# MINI_BLDC_DRV_POWER.net
KiCad netlist of a schematic drawn in Altium Designer
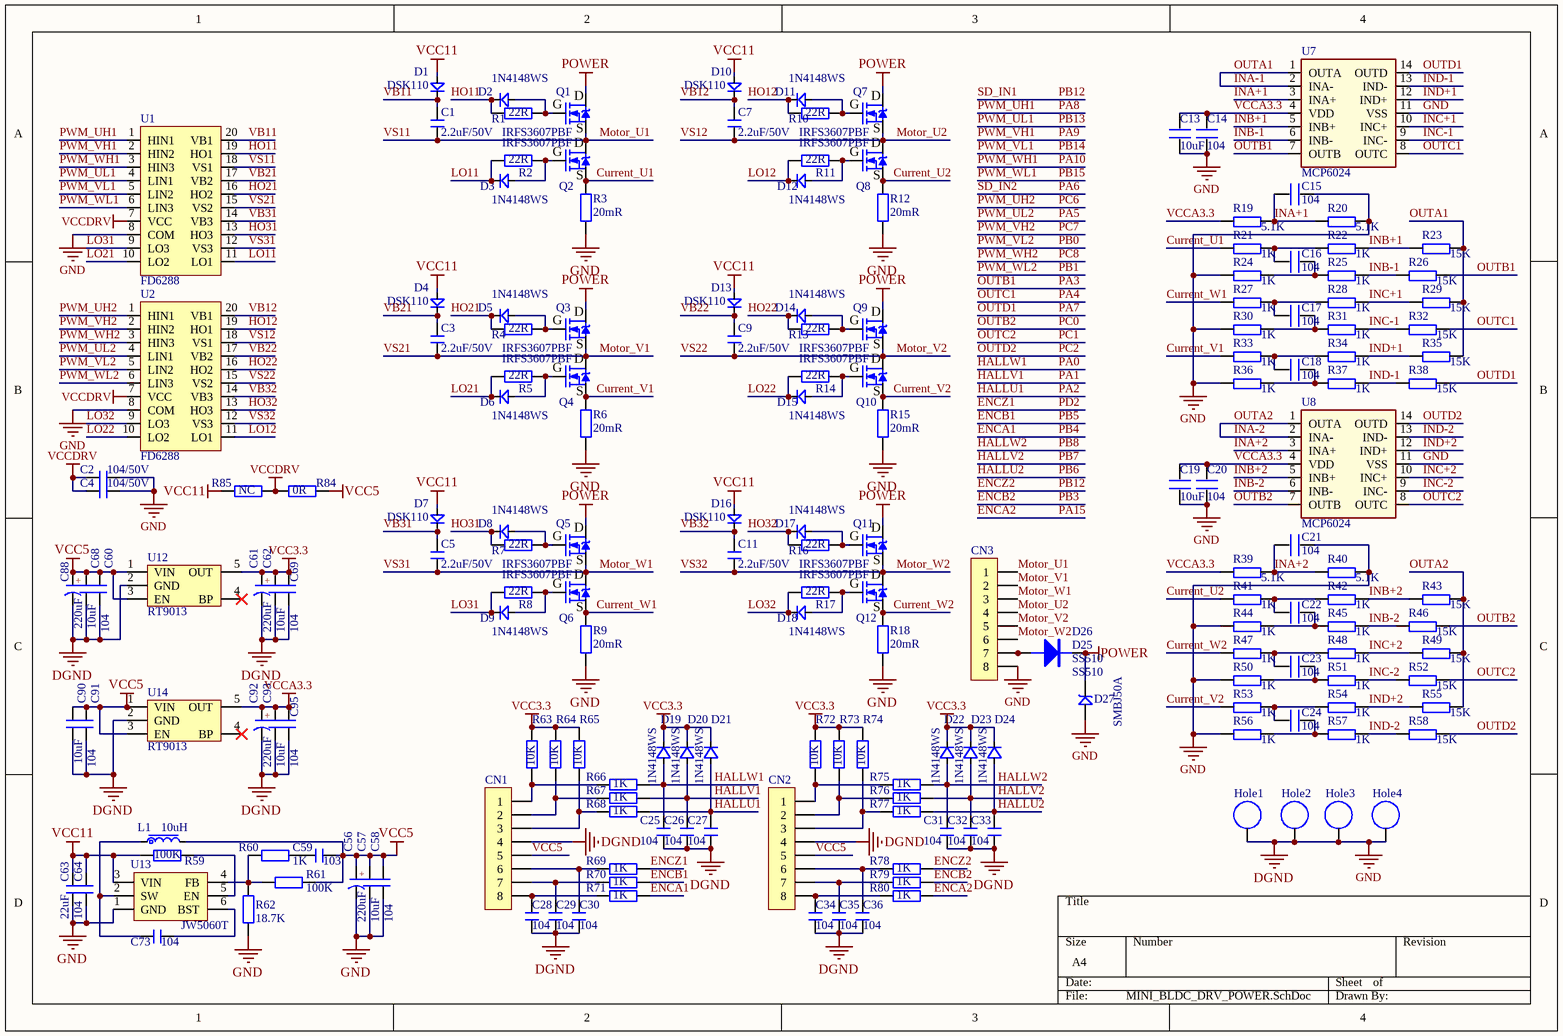
[diagram p0: MINI_BLDC_DRV_POWER.SchDoc]

(export (version "E")
  (design (tool "Eeschema 10.0.6"))
  (components
    (comp (ref "C1")
      (value "2.2uF/50V")
      (footprint "C 0603_L")
      (description "无极性贴片电容")
      (fields (field (name "版权归属") "源创客"))
      (libsource (lib "电阻-电容-电感") (part "C"))
    )
    (comp (ref "C2")
      (value "104/50V")
      (footprint "C 0603_L")
      (description "无极性贴片电容")
      (fields (field (name "版权归属") "源创客"))
      (libsource (lib "电阻-电容-电感") (part "C"))
    )
    (comp (ref "C3")
      (value "2.2uF/50V")
      (footprint "C 0603_L")
      (description "无极性贴片电容")
      (fields (field (name "版权归属") "源创客"))
      (libsource (lib "电阻-电容-电感") (part "C"))
    )
    (comp (ref "C4")
      (value "104/50V")
      (footprint "C 0603_L")
      (description "无极性贴片电容")
      (fields (field (name "版权归属") "源创客"))
      (libsource (lib "电阻-电容-电感") (part "C"))
    )
    (comp (ref "C5")
      (value "2.2uF/50V")
      (footprint "C 0603_L")
      (description "无极性贴片电容")
      (fields (field (name "版权归属") "源创客"))
      (libsource (lib "电阻-电容-电感") (part "C"))
    )
    (comp (ref "C7")
      (value "2.2uF/50V")
      (footprint "C 0603_L")
      (description "无极性贴片电容")
      (fields (field (name "版权归属") "源创客"))
      (libsource (lib "电阻-电容-电感") (part "C"))
    )
    (comp (ref "C9")
      (value "2.2uF/50V")
      (footprint "C 0603_L")
      (description "无极性贴片电容")
      (fields (field (name "版权归属") "源创客"))
      (libsource (lib "电阻-电容-电感") (part "C"))
    )
    (comp (ref "C11")
      (value "2.2uF/50V")
      (footprint "C 0603_L")
      (description "无极性贴片电容")
      (fields (field (name "版权归属") "源创客"))
      (libsource (lib "电阻-电容-电感") (part "C"))
    )
    (comp (ref "C13")
      (value "10uF")
      (footprint "C 0603_L")
      (libsource (lib "IMX6UL_ALPHA(底板)_V2.0") (part "C"))
    )
    (comp (ref "C14")
      (value "104")
      (footprint "C 0603_L")
      (libsource (lib "IMX6UL_ALPHA(底板)_V2.0") (part "C"))
    )
    (comp (ref "C15")
      (value "104")
      (footprint "C 0603_L")
      (libsource (lib "IMX6UL_ALPHA(底板)_V2.0") (part "C"))
    )
    (comp (ref "C16")
      (value "104")
      (footprint "C 0603_L")
      (libsource (lib "IMX6UL_ALPHA(底板)_V2.0") (part "C"))
    )
    (comp (ref "C17")
      (value "104")
      (footprint "C 0603_L")
      (libsource (lib "IMX6UL_ALPHA(底板)_V2.0") (part "C"))
    )
    (comp (ref "C18")
      (value "104")
      (footprint "C 0603_L")
      (libsource (lib "IMX6UL_ALPHA(底板)_V2.0") (part "C"))
    )
    (comp (ref "C19")
      (value "10uF")
      (footprint "C 0603_L")
      (libsource (lib "IMX6UL_ALPHA(底板)_V2.0") (part "C"))
    )
    (comp (ref "C20")
      (value "104")
      (footprint "C 0603_L")
      (libsource (lib "IMX6UL_ALPHA(底板)_V2.0") (part "C"))
    )
    (comp (ref "C21")
      (value "104")
      (footprint "C 0603_L")
      (libsource (lib "IMX6UL_ALPHA(底板)_V2.0") (part "C"))
    )
    (comp (ref "C22")
      (value "104")
      (footprint "C 0603_L")
      (libsource (lib "IMX6UL_ALPHA(底板)_V2.0") (part "C"))
    )
    (comp (ref "C23")
      (value "104")
      (footprint "C 0603_L")
      (libsource (lib "IMX6UL_ALPHA(底板)_V2.0") (part "C"))
    )
    (comp (ref "C24")
      (value "104")
      (footprint "C 0603_L")
      (libsource (lib "IMX6UL_ALPHA(底板)_V2.0") (part "C"))
    )
    (comp (ref "C25")
      (value "104")
      (footprint "C 0603_L")
      (description "无极性贴片电容")
      (fields (field (name "版权归属") "源创客"))
      (libsource (lib "电阻-电容-电感") (part "C"))
    )
    (comp (ref "C26")
      (value "104")
      (footprint "C 0603_L")
      (description "无极性贴片电容")
      (fields (field (name "版权归属") "源创客"))
      (libsource (lib "电阻-电容-电感") (part "C"))
    )
    (comp (ref "C27")
      (value "104")
      (footprint "C 0603_L")
      (description "无极性贴片电容")
      (fields (field (name "版权归属") "源创客"))
      (libsource (lib "电阻-电容-电感") (part "C"))
    )
    (comp (ref "C28")
      (value "104")
      (footprint "C 0603_L")
      (description "无极性贴片电容")
      (fields (field (name "版权归属") "源创客"))
      (libsource (lib "电阻-电容-电感") (part "C"))
    )
    (comp (ref "C29")
      (value "104")
      (footprint "C 0603_L")
      (description "无极性贴片电容")
      (fields (field (name "版权归属") "源创客"))
      (libsource (lib "电阻-电容-电感") (part "C"))
    )
    (comp (ref "C30")
      (value "104")
      (footprint "C 0603_L")
      (description "无极性贴片电容")
      (fields (field (name "版权归属") "源创客"))
      (libsource (lib "电阻-电容-电感") (part "C"))
    )
    (comp (ref "C31")
      (value "104")
      (footprint "C 0603_L")
      (description "无极性贴片电容")
      (fields (field (name "版权归属") "源创客"))
      (libsource (lib "电阻-电容-电感") (part "C"))
    )
    (comp (ref "C32")
      (value "104")
      (footprint "C 0603_L")
      (description "无极性贴片电容")
      (fields (field (name "版权归属") "源创客"))
      (libsource (lib "电阻-电容-电感") (part "C"))
    )
    (comp (ref "C33")
      (value "104")
      (footprint "C 0603_L")
      (description "无极性贴片电容")
      (fields (field (name "版权归属") "源创客"))
      (libsource (lib "电阻-电容-电感") (part "C"))
    )
    (comp (ref "C34")
      (value "104")
      (footprint "C 0603_L")
      (description "无极性贴片电容")
      (fields (field (name "版权归属") "源创客"))
      (libsource (lib "电阻-电容-电感") (part "C"))
    )
    (comp (ref "C35")
      (value "104")
      (footprint "C 0603_L")
      (description "无极性贴片电容")
      (fields (field (name "版权归属") "源创客"))
      (libsource (lib "电阻-电容-电感") (part "C"))
    )
    (comp (ref "C36")
      (value "104")
      (footprint "C 0603_L")
      (description "无极性贴片电容")
      (fields (field (name "版权归属") "源创客"))
      (libsource (lib "电阻-电容-电感") (part "C"))
    )
    (comp (ref "C56")
      (value "220uF")
      (footprint "CM D(6.3*5.4)")
      (description "贴片电解电容")
      (fields (field (name "版权归属") "源创客"))
      (libsource (lib "电阻-电容-电感") (part "C-CM"))
    )
    (comp (ref "C57")
      (value "10uF")
      (footprint "C 0603_L")
      (description "无极性贴片电容")
      (fields (field (name "版权归属") "源创客"))
      (libsource (lib "电阻-电容-电感") (part "C"))
    )
    (comp (ref "C58")
      (value "104")
      (footprint "C 0603_L")
      (description "无极性贴片电容")
      (fields (field (name "版权归属") "源创客"))
      (libsource (lib "电阻-电容-电感") (part "C"))
    )
    (comp (ref "C59")
      (value "103")
      (footprint "C 0603_L")
      (description "无极性贴片电容")
      (fields (field (name "版权归属") "源创客"))
      (libsource (lib "电阻-电容-电感") (part "C"))
    )
    (comp (ref "C60")
      (value "104")
      (footprint "C 0603_L")
      (description "无极性贴片电容")
      (fields (field (name "版权归属") "源创客"))
      (libsource (lib "电阻-电容-电感") (part "C"))
    )
    (comp (ref "C61")
      (value "220uF")
      (footprint "CM D(6.3*5.4)")
      (description "贴片电解电容")
      (fields (field (name "版权归属") "源创客"))
      (libsource (lib "电阻-电容-电感") (part "C-CM"))
    )
    (comp (ref "C62")
      (value "10uF")
      (footprint "C 0603_L")
      (description "无极性贴片电容")
      (fields (field (name "版权归属") "源创客"))
      (libsource (lib "电阻-电容-电感") (part "C"))
    )
    (comp (ref "C63")
      (value "22uF")
      (footprint "C 0805_L")
      (description "无极性贴片电容")
      (fields (field (name "版权归属") "源创客"))
      (libsource (lib "电阻-电容-电感") (part "C"))
    )
    (comp (ref "C64")
      (value "104")
      (footprint "C 0603_L")
      (description "无极性贴片电容")
      (fields (field (name "版权归属") "源创客"))
      (libsource (lib "电阻-电容-电感") (part "C"))
    )
    (comp (ref "C68")
      (value "10uF")
      (footprint "C 0603_L")
      (description "无极性贴片电容")
      (fields (field (name "版权归属") "源创客"))
      (libsource (lib "电阻-电容-电感") (part "C"))
    )
    (comp (ref "C69")
      (value "104")
      (footprint "C 0603_L")
      (description "无极性贴片电容")
      (fields (field (name "版权归属") "源创客"))
      (libsource (lib "电阻-电容-电感") (part "C"))
    )
    (comp (ref "C73")
      (value "104")
      (footprint "C 0603_L")
      (description "无极性贴片电容")
      (fields (field (name "版权归属") "源创客"))
      (libsource (lib "电阻-电容-电感") (part "C"))
    )
    (comp (ref "C88")
      (value "220uF")
      (footprint "CM D(6.3*5.4)")
      (description "贴片电解电容")
      (fields (field (name "版权归属") "源创客"))
      (libsource (lib "电阻-电容-电感") (part "C-CM"))
    )
    (comp (ref "C90")
      (value "10uF")
      (footprint "C 0603_L")
      (description "无极性贴片电容")
      (fields (field (name "版权归属") "源创客"))
      (libsource (lib "电阻-电容-电感") (part "C"))
    )
    (comp (ref "C91")
      (value "104")
      (footprint "C 0603_L")
      (description "无极性贴片电容")
      (fields (field (name "版权归属") "源创客"))
      (libsource (lib "电阻-电容-电感") (part "C"))
    )
    (comp (ref "C92")
      (value "220uF")
      (footprint "CM D(6.3*5.4)")
      (description "贴片电解电容")
      (fields (field (name "版权归属") "源创客"))
      (libsource (lib "电阻-电容-电感") (part "C-CM"))
    )
    (comp (ref "C93")
      (value "10uF")
      (footprint "C 0603_L")
      (description "无极性贴片电容")
      (fields (field (name "版权归属") "源创客"))
      (libsource (lib "电阻-电容-电感") (part "C"))
    )
    (comp (ref "C95")
      (value "104")
      (footprint "C 0603_L")
      (description "无极性贴片电容")
      (fields (field (name "版权归属") "源创客"))
      (libsource (lib "电阻-电容-电感") (part "C"))
    )
    (comp (ref "CN1")
      (value "HDR-1X8")
      (footprint "SH1.0 S-W-8P")
      (description "8P接插件")
      (fields (field (name "版权归属") "源创客"))
      (libsource (lib "接插件") (part "Header 8"))
    )
    (comp (ref "CN2")
      (value "HDR-1X8")
      (footprint "SH1.0 S-W-8P")
      (description "8P接插件")
      (fields (field (name "版权归属") "源创客"))
      (libsource (lib "接插件") (part "Header 8"))
    )
    (comp (ref "CN3")
      (value "HDR-1X8")
      (footprint "KF7620-8P")
      (description "8P接插件")
      (fields (field (name "版权归属") "源创客"))
      (libsource (lib "接插件") (part "Header 8"))
    )
    (comp (ref "D1")
      (value "DSK110")
      (footprint "SOD-123F")
      (description "通用二极管 100V-1A")
      (fields (field (name "版权归属") "源创客"))
      (libsource (lib "二极管-整流桥") (part "DSK110"))
    )
    (comp (ref "D2")
      (value "1N4148WS")
      (footprint "SOD-323")
      (description "通用二极管 700V-1A")
      (fields (field (name "版权归属") "源创客"))
      (libsource (lib "二极管-整流桥") (part "FR107"))
    )
    (comp (ref "D3")
      (value "1N4148WS")
      (footprint "SOD-323")
      (description "通用二极管 700V-1A")
      (fields (field (name "版权归属") "源创客"))
      (libsource (lib "二极管-整流桥") (part "FR107"))
    )
    (comp (ref "D4")
      (value "DSK110")
      (footprint "SOD-123F")
      (description "通用二极管 100V-1A")
      (fields (field (name "版权归属") "源创客"))
      (libsource (lib "二极管-整流桥") (part "DSK110"))
    )
    (comp (ref "D5")
      (value "1N4148WS")
      (footprint "SOD-323")
      (description "通用二极管 700V-1A")
      (fields (field (name "版权归属") "源创客"))
      (libsource (lib "二极管-整流桥") (part "FR107"))
    )
    (comp (ref "D6")
      (value "1N4148WS")
      (footprint "SOD-323")
      (description "通用二极管 700V-1A")
      (fields (field (name "版权归属") "源创客"))
      (libsource (lib "二极管-整流桥") (part "FR107"))
    )
    (comp (ref "D7")
      (value "DSK110")
      (footprint "SOD-123F")
      (description "通用二极管 100V-1A")
      (fields (field (name "版权归属") "源创客"))
      (libsource (lib "二极管-整流桥") (part "DSK110"))
    )
    (comp (ref "D8")
      (value "1N4148WS")
      (footprint "SOD-323")
      (description "通用二极管 700V-1A")
      (fields (field (name "版权归属") "源创客"))
      (libsource (lib "二极管-整流桥") (part "FR107"))
    )
    (comp (ref "D9")
      (value "1N4148WS")
      (footprint "SOD-323")
      (description "通用二极管 700V-1A")
      (fields (field (name "版权归属") "源创客"))
      (libsource (lib "二极管-整流桥") (part "FR107"))
    )
    (comp (ref "D10")
      (value "DSK110")
      (footprint "SOD-123F")
      (description "通用二极管 100V-1A")
      (fields (field (name "版权归属") "源创客"))
      (libsource (lib "二极管-整流桥") (part "DSK110"))
    )
    (comp (ref "D11")
      (value "1N4148WS")
      (footprint "SOD-323")
      (description "通用二极管 700V-1A")
      (fields (field (name "版权归属") "源创客"))
      (libsource (lib "二极管-整流桥") (part "FR107"))
    )
    (comp (ref "D12")
      (value "1N4148WS")
      (footprint "SOD-323")
      (description "通用二极管 700V-1A")
      (fields (field (name "版权归属") "源创客"))
      (libsource (lib "二极管-整流桥") (part "FR107"))
    )
    (comp (ref "D13")
      (value "DSK110")
      (footprint "SOD-123F")
      (description "通用二极管 100V-1A")
      (fields (field (name "版权归属") "源创客"))
      (libsource (lib "二极管-整流桥") (part "DSK110"))
    )
    (comp (ref "D14")
      (value "1N4148WS")
      (footprint "SOD-323")
      (description "通用二极管 700V-1A")
      (fields (field (name "版权归属") "源创客"))
      (libsource (lib "二极管-整流桥") (part "FR107"))
    )
    (comp (ref "D15")
      (value "1N4148WS")
      (footprint "SOD-323")
      (description "通用二极管 700V-1A")
      (fields (field (name "版权归属") "源创客"))
      (libsource (lib "二极管-整流桥") (part "FR107"))
    )
    (comp (ref "D16")
      (value "DSK110")
      (footprint "SOD-123F")
      (description "通用二极管 100V-1A")
      (fields (field (name "版权归属") "源创客"))
      (libsource (lib "二极管-整流桥") (part "DSK110"))
    )
    (comp (ref "D17")
      (value "1N4148WS")
      (footprint "SOD-323")
      (description "通用二极管 700V-1A")
      (fields (field (name "版权归属") "源创客"))
      (libsource (lib "二极管-整流桥") (part "FR107"))
    )
    (comp (ref "D18")
      (value "1N4148WS")
      (footprint "SOD-323")
      (description "通用二极管 700V-1A")
      (fields (field (name "版权归属") "源创客"))
      (libsource (lib "二极管-整流桥") (part "FR107"))
    )
    (comp (ref "D19")
      (value "1N4148WS")
      (footprint "SOD-323")
      (description "通用二极管 1000V-1A")
      (fields (field (name "版权归属") "源创客"))
      (libsource (lib "二极管-整流桥") (part "RS1M"))
    )
    (comp (ref "D20")
      (value "1N4148WS")
      (footprint "SOD-323")
      (description "通用二极管 1000V-1A")
      (fields (field (name "版权归属") "源创客"))
      (libsource (lib "二极管-整流桥") (part "RS1M"))
    )
    (comp (ref "D21")
      (value "1N4148WS")
      (footprint "SOD-323")
      (description "通用二极管 1000V-1A")
      (fields (field (name "版权归属") "源创客"))
      (libsource (lib "二极管-整流桥") (part "RS1M"))
    )
    (comp (ref "D22")
      (value "1N4148WS")
      (footprint "SOD-323")
      (description "通用二极管 1000V-1A")
      (fields (field (name "版权归属") "源创客"))
      (libsource (lib "二极管-整流桥") (part "RS1M"))
    )
    (comp (ref "D23")
      (value "1N4148WS")
      (footprint "SOD-323")
      (description "通用二极管 1000V-1A")
      (fields (field (name "版权归属") "源创客"))
      (libsource (lib "二极管-整流桥") (part "RS1M"))
    )
    (comp (ref "D24")
      (value "1N4148WS")
      (footprint "SOD-323")
      (description "通用二极管 1000V-1A")
      (fields (field (name "版权归属") "源创客"))
      (libsource (lib "二极管-整流桥") (part "RS1M"))
    )
    (comp (ref "D25")
      (value "SS510")
      (footprint "LovelessingPcb:SMB")
      (description "整流二极管")
      (libsource (lib "LovelessingSch") (part "DIODE"))
    )
    (comp (ref "D26")
      (value "SS510")
      (footprint "LovelessingPcb:SMB")
      (description "整流二极管")
      (libsource (lib "LovelessingSch") (part "DIODE"))
    )
    (comp (ref "D27")
      (value "SMBJ50A")
      (footprint "LovelessingPcb:SMC")
      (description "TVS")
      (libsource (lib "IMX6UL_ALPHA_V1.4") (part "SMBJ"))
    )
    (comp (ref "Hole1")
      (value "M3孔")
      (footprint "M3x4_L")
      (description "铜柱孔")
      (fields (field (name "版权归属") "源创客"))
      (libsource (lib "未分类器件") (part "M3"))
    )
    (comp (ref "Hole2")
      (value "M3孔")
      (footprint "M3x4_L")
      (description "铜柱孔")
      (fields (field (name "版权归属") "源创客"))
      (libsource (lib "未分类器件") (part "M3"))
    )
    (comp (ref "Hole3")
      (value "M3孔")
      (footprint "M3x4_L")
      (description "铜柱孔")
      (fields (field (name "版权归属") "源创客"))
      (libsource (lib "未分类器件") (part "M3"))
    )
    (comp (ref "Hole4")
      (value "M3孔")
      (footprint "M3x4_L")
      (description "铜柱孔")
      (fields (field (name "版权归属") "源创客"))
      (libsource (lib "未分类器件") (part "M3"))
    )
    (comp (ref "L1")
      (value "10uH")
      (footprint "L-SMD-0420")
      (description "功率屏蔽电感")
      (fields (field (name "版权归属") "源创客"))
      (libsource (lib "电阻-电容-电感") (part "L-CDRH"))
    )
    (comp (ref "Q1")
      (value "IRFS3607PBF")
      (footprint "TO263_3B")
      (description "NMOS 75V+80A 7.4mΩ")
      (fields (field (name "版权归属") "源创客"))
      (libsource (lib "场效应管-可控硅") (part "IRFS3607PBF"))
    )
    (comp (ref "Q2")
      (value "IRFS3607PBF")
      (footprint "TO263_3B")
      (description "NMOS 75V+80A 7.4mΩ")
      (fields (field (name "版权归属") "源创客"))
      (libsource (lib "场效应管-可控硅") (part "IRFS3607PBF"))
    )
    (comp (ref "Q3")
      (value "IRFS3607PBF")
      (footprint "TO263_3B")
      (description "NMOS 75V+80A 7.4mΩ")
      (fields (field (name "版权归属") "源创客"))
      (libsource (lib "场效应管-可控硅") (part "IRFS3607PBF"))
    )
    (comp (ref "Q4")
      (value "IRFS3607PBF")
      (footprint "TO263_3B")
      (description "NMOS 75V+80A 7.4mΩ")
      (fields (field (name "版权归属") "源创客"))
      (libsource (lib "场效应管-可控硅") (part "IRFS3607PBF"))
    )
    (comp (ref "Q5")
      (value "IRFS3607PBF")
      (footprint "TO263_3B")
      (description "NMOS 75V+80A 7.4mΩ")
      (fields (field (name "版权归属") "源创客"))
      (libsource (lib "场效应管-可控硅") (part "IRFS3607PBF"))
    )
    (comp (ref "Q6")
      (value "IRFS3607PBF")
      (footprint "TO263_3B")
      (description "NMOS 75V+80A 7.4mΩ")
      (fields (field (name "版权归属") "源创客"))
      (libsource (lib "场效应管-可控硅") (part "IRFS3607PBF"))
    )
    (comp (ref "Q7")
      (value "IRFS3607PBF")
      (footprint "TO263_3B")
      (description "NMOS 75V+80A 7.4mΩ")
      (fields (field (name "版权归属") "源创客"))
      (libsource (lib "场效应管-可控硅") (part "IRFS3607PBF"))
    )
    (comp (ref "Q8")
      (value "IRFS3607PBF")
      (footprint "TO263_3B")
      (description "NMOS 75V+80A 7.4mΩ")
      (fields (field (name "版权归属") "源创客"))
      (libsource (lib "场效应管-可控硅") (part "IRFS3607PBF"))
    )
    (comp (ref "Q9")
      (value "IRFS3607PBF")
      (footprint "TO263_3B")
      (description "NMOS 75V+80A 7.4mΩ")
      (fields (field (name "版权归属") "源创客"))
      (libsource (lib "场效应管-可控硅") (part "IRFS3607PBF"))
    )
    (comp (ref "Q10")
      (value "IRFS3607PBF")
      (footprint "TO263_3B")
      (description "NMOS 75V+80A 7.4mΩ")
      (fields (field (name "版权归属") "源创客"))
      (libsource (lib "场效应管-可控硅") (part "IRFS3607PBF"))
    )
    (comp (ref "Q11")
      (value "IRFS3607PBF")
      (footprint "TO263_3B")
      (description "NMOS 75V+80A 7.4mΩ")
      (fields (field (name "版权归属") "源创客"))
      (libsource (lib "场效应管-可控硅") (part "IRFS3607PBF"))
    )
    (comp (ref "Q12")
      (value "IRFS3607PBF")
      (footprint "TO263_3B")
      (description "NMOS 75V+80A 7.4mΩ")
      (fields (field (name "版权归属") "源创客"))
      (libsource (lib "场效应管-可控硅") (part "IRFS3607PBF"))
    )
    (comp (ref "R1")
      (value "22R")
      (footprint "R 0603_L")
      (description "贴片电阻")
      (fields (field (name "版权归属") "源创客"))
      (libsource (lib "电阻-电容-电感") (part "R"))
    )
    (comp (ref "R2")
      (value "22R")
      (footprint "R 0603_L")
      (description "贴片电阻")
      (fields (field (name "版权归属") "源创客"))
      (libsource (lib "电阻-电容-电感") (part "R"))
    )
    (comp (ref "R3")
      (value "20mR")
      (footprint "R 2512_L")
      (description "贴片电阻")
      (fields (field (name "版权归属") "源创客"))
      (libsource (lib "电阻-电容-电感") (part "R"))
    )
    (comp (ref "R4")
      (value "22R")
      (footprint "R 0603_L")
      (description "贴片电阻")
      (fields (field (name "版权归属") "源创客"))
      (libsource (lib "电阻-电容-电感") (part "R"))
    )
    (comp (ref "R5")
      (value "22R")
      (footprint "R 0603_L")
      (description "贴片电阻")
      (fields (field (name "版权归属") "源创客"))
      (libsource (lib "电阻-电容-电感") (part "R"))
    )
    (comp (ref "R6")
      (value "20mR")
      (footprint "R 2512_L")
      (description "贴片电阻")
      (fields (field (name "版权归属") "源创客"))
      (libsource (lib "电阻-电容-电感") (part "R"))
    )
    (comp (ref "R7")
      (value "22R")
      (footprint "R 0603_L")
      (description "贴片电阻")
      (fields (field (name "版权归属") "源创客"))
      (libsource (lib "电阻-电容-电感") (part "R"))
    )
    (comp (ref "R8")
      (value "22R")
      (footprint "R 0603_L")
      (description "贴片电阻")
      (fields (field (name "版权归属") "源创客"))
      (libsource (lib "电阻-电容-电感") (part "R"))
    )
    (comp (ref "R9")
      (value "20mR")
      (footprint "R 2512_L")
      (description "贴片电阻")
      (fields (field (name "版权归属") "源创客"))
      (libsource (lib "电阻-电容-电感") (part "R"))
    )
    (comp (ref "R10")
      (value "22R")
      (footprint "R 0603_L")
      (description "贴片电阻")
      (fields (field (name "版权归属") "源创客"))
      (libsource (lib "电阻-电容-电感") (part "R"))
    )
    (comp (ref "R11")
      (value "22R")
      (footprint "R 0603_L")
      (description "贴片电阻")
      (fields (field (name "版权归属") "源创客"))
      (libsource (lib "电阻-电容-电感") (part "R"))
    )
    (comp (ref "R12")
      (value "20mR")
      (footprint "R 2512_L")
      (description "贴片电阻")
      (fields (field (name "版权归属") "源创客"))
      (libsource (lib "电阻-电容-电感") (part "R"))
    )
    (comp (ref "R13")
      (value "22R")
      (footprint "R 0603_L")
      (description "贴片电阻")
      (fields (field (name "版权归属") "源创客"))
      (libsource (lib "电阻-电容-电感") (part "R"))
    )
    (comp (ref "R14")
      (value "22R")
      (footprint "R 0603_L")
      (description "贴片电阻")
      (fields (field (name "版权归属") "源创客"))
      (libsource (lib "电阻-电容-电感") (part "R"))
    )
    (comp (ref "R15")
      (value "20mR")
      (footprint "R 2512_L")
      (description "贴片电阻")
      (fields (field (name "版权归属") "源创客"))
      (libsource (lib "电阻-电容-电感") (part "R"))
    )
    (comp (ref "R16")
      (value "22R")
      (footprint "R 0603_L")
      (description "贴片电阻")
      (fields (field (name "版权归属") "源创客"))
      (libsource (lib "电阻-电容-电感") (part "R"))
    )
    (comp (ref "R17")
      (value "22R")
      (footprint "R 0603_L")
      (description "贴片电阻")
      (fields (field (name "版权归属") "源创客"))
      (libsource (lib "电阻-电容-电感") (part "R"))
    )
    (comp (ref "R18")
      (value "20mR")
      (footprint "R 2512_L")
      (description "贴片电阻")
      (fields (field (name "版权归属") "源创客"))
      (libsource (lib "电阻-电容-电感") (part "R"))
    )
    (comp (ref "R19")
      (value "5.1K")
      (footprint "R 0603_L")
      (libsource (lib "IMX6UL_ALPHA(底板)_V2.0") (part "R"))
    )
    (comp (ref "R20")
      (value "5.1K")
      (footprint "R 0603_L")
      (libsource (lib "IMX6UL_ALPHA(底板)_V2.0") (part "R"))
    )
    (comp (ref "R21")
      (value "1K")
      (footprint "R 0603_L")
      (libsource (lib "IMX6UL_ALPHA(底板)_V2.0") (part "R"))
    )
    (comp (ref "R22")
      (value "1K")
      (footprint "R 0603_L")
      (libsource (lib "IMX6UL_ALPHA(底板)_V2.0") (part "R"))
    )
    (comp (ref "R23")
      (value "15K")
      (footprint "R 0603_L")
      (libsource (lib "IMX6UL_ALPHA(底板)_V2.0") (part "R"))
    )
    (comp (ref "R24")
      (value "1K")
      (footprint "R 0603_L")
      (libsource (lib "IMX6UL_ALPHA(底板)_V2.0") (part "R"))
    )
    (comp (ref "R25")
      (value "1K")
      (footprint "R 0603_L")
      (libsource (lib "IMX6UL_ALPHA(底板)_V2.0") (part "R"))
    )
    (comp (ref "R26")
      (value "15K")
      (footprint "R 0603_L")
      (libsource (lib "IMX6UL_ALPHA(底板)_V2.0") (part "R"))
    )
    (comp (ref "R27")
      (value "1K")
      (footprint "R 0603_L")
      (libsource (lib "IMX6UL_ALPHA(底板)_V2.0") (part "R"))
    )
    (comp (ref "R28")
      (value "1K")
      (footprint "R 0603_L")
      (libsource (lib "IMX6UL_ALPHA(底板)_V2.0") (part "R"))
    )
    (comp (ref "R29")
      (value "15K")
      (footprint "R 0603_L")
      (libsource (lib "IMX6UL_ALPHA(底板)_V2.0") (part "R"))
    )
    (comp (ref "R30")
      (value "1K")
      (footprint "R 0603_L")
      (libsource (lib "IMX6UL_ALPHA(底板)_V2.0") (part "R"))
    )
    (comp (ref "R31")
      (value "1K")
      (footprint "R 0603_L")
      (libsource (lib "IMX6UL_ALPHA(底板)_V2.0") (part "R"))
    )
    (comp (ref "R32")
      (value "15K")
      (footprint "R 0603_L")
      (libsource (lib "IMX6UL_ALPHA(底板)_V2.0") (part "R"))
    )
    (comp (ref "R33")
      (value "1K")
      (footprint "R 0603_L")
      (libsource (lib "IMX6UL_ALPHA(底板)_V2.0") (part "R"))
    )
    (comp (ref "R34")
      (value "1K")
      (footprint "R 0603_L")
      (libsource (lib "IMX6UL_ALPHA(底板)_V2.0") (part "R"))
    )
    (comp (ref "R35")
      (value "15K")
      (footprint "R 0603_L")
      (libsource (lib "IMX6UL_ALPHA(底板)_V2.0") (part "R"))
    )
    (comp (ref "R36")
      (value "1K")
      (footprint "R 0603_L")
      (libsource (lib "IMX6UL_ALPHA(底板)_V2.0") (part "R"))
    )
    (comp (ref "R37")
      (value "1K")
      (footprint "R 0603_L")
      (libsource (lib "IMX6UL_ALPHA(底板)_V2.0") (part "R"))
    )
    (comp (ref "R38")
      (value "15K")
      (footprint "R 0603_L")
      (libsource (lib "IMX6UL_ALPHA(底板)_V2.0") (part "R"))
    )
    (comp (ref "R39")
      (value "5.1K")
      (footprint "R 0603_L")
      (libsource (lib "IMX6UL_ALPHA(底板)_V2.0") (part "R"))
    )
    (comp (ref "R40")
      (value "5.1K")
      (footprint "R 0603_L")
      (libsource (lib "IMX6UL_ALPHA(底板)_V2.0") (part "R"))
    )
    (comp (ref "R41")
      (value "1K")
      (footprint "R 0603_L")
      (libsource (lib "IMX6UL_ALPHA(底板)_V2.0") (part "R"))
    )
    (comp (ref "R42")
      (value "1K")
      (footprint "R 0603_L")
      (libsource (lib "IMX6UL_ALPHA(底板)_V2.0") (part "R"))
    )
    (comp (ref "R43")
      (value "15K")
      (footprint "R 0603_L")
      (libsource (lib "IMX6UL_ALPHA(底板)_V2.0") (part "R"))
    )
    (comp (ref "R44")
      (value "1K")
      (footprint "R 0603_L")
      (libsource (lib "IMX6UL_ALPHA(底板)_V2.0") (part "R"))
    )
    (comp (ref "R45")
      (value "1K")
      (footprint "R 0603_L")
      (libsource (lib "IMX6UL_ALPHA(底板)_V2.0") (part "R"))
    )
    (comp (ref "R46")
      (value "15K")
      (footprint "R 0603_L")
      (libsource (lib "IMX6UL_ALPHA(底板)_V2.0") (part "R"))
    )
    (comp (ref "R47")
      (value "1K")
      (footprint "R 0603_L")
      (libsource (lib "IMX6UL_ALPHA(底板)_V2.0") (part "R"))
    )
    (comp (ref "R48")
      (value "1K")
      (footprint "R 0603_L")
      (libsource (lib "IMX6UL_ALPHA(底板)_V2.0") (part "R"))
    )
    (comp (ref "R49")
      (value "15K")
      (footprint "R 0603_L")
      (libsource (lib "IMX6UL_ALPHA(底板)_V2.0") (part "R"))
    )
    (comp (ref "R50")
      (value "1K")
      (footprint "R 0603_L")
      (libsource (lib "IMX6UL_ALPHA(底板)_V2.0") (part "R"))
    )
    (comp (ref "R51")
      (value "1K")
      (footprint "R 0603_L")
      (libsource (lib "IMX6UL_ALPHA(底板)_V2.0") (part "R"))
    )
    (comp (ref "R52")
      (value "15K")
      (footprint "R 0603_L")
      (libsource (lib "IMX6UL_ALPHA(底板)_V2.0") (part "R"))
    )
    (comp (ref "R53")
      (value "1K")
      (footprint "R 0603_L")
      (libsource (lib "IMX6UL_ALPHA(底板)_V2.0") (part "R"))
    )
    (comp (ref "R54")
      (value "1K")
      (footprint "R 0603_L")
      (libsource (lib "IMX6UL_ALPHA(底板)_V2.0") (part "R"))
    )
    (comp (ref "R55")
      (value "15K")
      (footprint "R 0603_L")
      (libsource (lib "IMX6UL_ALPHA(底板)_V2.0") (part "R"))
    )
    (comp (ref "R56")
      (value "1K")
      (footprint "R 0603_L")
      (libsource (lib "IMX6UL_ALPHA(底板)_V2.0") (part "R"))
    )
    (comp (ref "R57")
      (value "1K")
      (footprint "R 0603_L")
      (libsource (lib "IMX6UL_ALPHA(底板)_V2.0") (part "R"))
    )
    (comp (ref "R58")
      (value "15K")
      (footprint "R 0603_L")
      (libsource (lib "IMX6UL_ALPHA(底板)_V2.0") (part "R"))
    )
    (comp (ref "R59")
      (value "100K")
      (footprint "R 0603_L")
      (description "贴片电阻")
      (fields (field (name "版权归属") "源创客"))
      (libsource (lib "电阻-电容-电感") (part "R"))
    )
    (comp (ref "R60")
      (value "1K")
      (footprint "R 0603_L")
      (description "贴片电阻")
      (fields (field (name "版权归属") "源创客"))
      (libsource (lib "电阻-电容-电感") (part "R"))
    )
    (comp (ref "R61")
      (value "100K")
      (footprint "R 0603_L")
      (description "贴片电阻")
      (fields (field (name "版权归属") "源创客"))
      (libsource (lib "电阻-电容-电感") (part "R"))
    )
    (comp (ref "R62")
      (value "18.7K")
      (footprint "R 0603_L")
      (description "贴片电阻")
      (fields (field (name "版权归属") "源创客"))
      (libsource (lib "电阻-电容-电感") (part "R"))
    )
    (comp (ref "R63")
      (value "10K")
      (footprint "R 0603_L")
      (description "贴片电阻")
      (fields (field (name "版权归属") "源创客"))
      (libsource (lib "电阻-电容-电感") (part "R"))
    )
    (comp (ref "R64")
      (value "10K")
      (footprint "R 0603_L")
      (description "贴片电阻")
      (fields (field (name "版权归属") "源创客"))
      (libsource (lib "电阻-电容-电感") (part "R"))
    )
    (comp (ref "R65")
      (value "10K")
      (footprint "R 0603_L")
      (description "贴片电阻")
      (fields (field (name "版权归属") "源创客"))
      (libsource (lib "电阻-电容-电感") (part "R"))
    )
    (comp (ref "R66")
      (value "1K")
      (footprint "R 0603_L")
      (description "贴片电阻")
      (fields (field (name "版权归属") "源创客"))
      (libsource (lib "电阻-电容-电感") (part "R"))
    )
    (comp (ref "R67")
      (value "1K")
      (footprint "R 0603_L")
      (description "贴片电阻")
      (fields (field (name "版权归属") "源创客"))
      (libsource (lib "电阻-电容-电感") (part "R"))
    )
    (comp (ref "R68")
      (value "1K")
      (footprint "R 0603_L")
      (description "贴片电阻")
      (fields (field (name "版权归属") "源创客"))
      (libsource (lib "电阻-电容-电感") (part "R"))
    )
    (comp (ref "R69")
      (value "1K")
      (footprint "R 0603_L")
      (description "贴片电阻")
      (fields (field (name "版权归属") "源创客"))
      (libsource (lib "电阻-电容-电感") (part "R"))
    )
    (comp (ref "R70")
      (value "1K")
      (footprint "R 0603_L")
      (description "贴片电阻")
      (fields (field (name "版权归属") "源创客"))
      (libsource (lib "电阻-电容-电感") (part "R"))
    )
    (comp (ref "R71")
      (value "1K")
      (footprint "R 0603_L")
      (description "贴片电阻")
      (fields (field (name "版权归属") "源创客"))
      (libsource (lib "电阻-电容-电感") (part "R"))
    )
    (comp (ref "R72")
      (value "10K")
      (footprint "R 0603_L")
      (description "贴片电阻")
      (fields (field (name "版权归属") "源创客"))
      (libsource (lib "电阻-电容-电感") (part "R"))
    )
    (comp (ref "R73")
      (value "10K")
      (footprint "R 0603_L")
      (description "贴片电阻")
      (fields (field (name "版权归属") "源创客"))
      (libsource (lib "电阻-电容-电感") (part "R"))
    )
    (comp (ref "R74")
      (value "10K")
      (footprint "R 0603_L")
      (description "贴片电阻")
      (fields (field (name "版权归属") "源创客"))
      (libsource (lib "电阻-电容-电感") (part "R"))
    )
    (comp (ref "R75")
      (value "1K")
      (footprint "R 0603_L")
      (description "贴片电阻")
      (fields (field (name "版权归属") "源创客"))
      (libsource (lib "电阻-电容-电感") (part "R"))
    )
    (comp (ref "R76")
      (value "1K")
      (footprint "R 0603_L")
      (description "贴片电阻")
      (fields (field (name "版权归属") "源创客"))
      (libsource (lib "电阻-电容-电感") (part "R"))
    )
    (comp (ref "R77")
      (value "1K")
      (footprint "R 0603_L")
      (description "贴片电阻")
      (fields (field (name "版权归属") "源创客"))
      (libsource (lib "电阻-电容-电感") (part "R"))
    )
    (comp (ref "R78")
      (value "1K")
      (footprint "R 0603_L")
      (description "贴片电阻")
      (fields (field (name "版权归属") "源创客"))
      (libsource (lib "电阻-电容-电感") (part "R"))
    )
    (comp (ref "R79")
      (value "1K")
      (footprint "R 0603_L")
      (description "贴片电阻")
      (fields (field (name "版权归属") "源创客"))
      (libsource (lib "电阻-电容-电感") (part "R"))
    )
    (comp (ref "R80")
      (value "1K")
      (footprint "R 0603_L")
      (description "贴片电阻")
      (fields (field (name "版权归属") "源创客"))
      (libsource (lib "电阻-电容-电感") (part "R"))
    )
    (comp (ref "R84")
      (value "0R")
      (footprint "R 0603_L")
      (description "贴片电阻")
      (fields (field (name "版权归属") "源创客"))
      (libsource (lib "电阻-电容-电感") (part "R"))
    )
    (comp (ref "R85")
      (value "NC")
      (footprint "R 0603_L")
      (description "贴片电阻")
      (fields (field (name "版权归属") "源创客"))
      (libsource (lib "电阻-电容-电感") (part "R"))
    )
    (comp (ref "U1") (value "FD6288") (footprint "TSSOP20_L") (libsource (lib "MINIBLDC") (part "FD6288")))
    (comp (ref "U2") (value "FD6288") (footprint "TSSOP20_L") (libsource (lib "MINIBLDC") (part "FD6288")))
    (comp (ref "U7") (value "MCP6024") (footprint "SOP14_L") (libsource (lib "MINIBLDC") (part "MCP6024")))
    (comp (ref "U8") (value "MCP6024") (footprint "SOP14_L") (libsource (lib "MINIBLDC") (part "MCP6024")))
    (comp (ref "U12")
      (value "RT9013")
      (footprint "SOT23-5N")
      (description "LDO")
      (fields (field (name "版权归属") "源创客"))
      (libsource (lib "LDO和DCDC") (part "LDO RT9193"))
    )
    (comp (ref "U13")
      (value "JW5060T")
      (footprint "SOT23-6L")
      (description "DC降压芯片")
      (libsource (lib "LDO和DCDC") (part "DC JW5060T_6"))
    )
    (comp (ref "U14")
      (value "RT9013")
      (footprint "SOT23-5N")
      (description "LDO")
      (fields (field (name "版权归属") "源创客"))
      (libsource (lib "LDO和DCDC") (part "LDO RT9193"))
    )
  )
  (nets
    (net (code "1") (name "/Current_U1") (class "Default")
      (node (ref "Q2") (pin "3") (pinfunction "S_3") (pintype "passive"))
      (node (ref "R21") (pin "1") (pintype "passive"))
      (node (ref "R3") (pin "2") (pinfunction "2_2") (pintype "passive"))
    )
    (net (code "2") (name "/Current_U2") (class "Default")
      (node (ref "Q8") (pin "3") (pinfunction "S_3") (pintype "passive"))
      (node (ref "R12") (pin "2") (pinfunction "2_2") (pintype "passive"))
      (node (ref "R41") (pin "1") (pintype "passive"))
    )
    (net (code "3") (name "/Current_V1") (class "Default")
      (node (ref "Q4") (pin "3") (pinfunction "S_3") (pintype "passive"))
      (node (ref "R33") (pin "1") (pintype "passive"))
      (node (ref "R6") (pin "2") (pinfunction "2_2") (pintype "passive"))
    )
    (net (code "4") (name "/Current_V2") (class "Default")
      (node (ref "Q10") (pin "3") (pinfunction "S_3") (pintype "passive"))
      (node (ref "R15") (pin "2") (pinfunction "2_2") (pintype "passive"))
      (node (ref "R53") (pin "1") (pintype "passive"))
    )
    (net (code "5") (name "/Current_W1") (class "Default")
      (node (ref "Q6") (pin "3") (pinfunction "S_3") (pintype "passive"))
      (node (ref "R27") (pin "1") (pintype "passive"))
      (node (ref "R9") (pin "2") (pinfunction "2_2") (pintype "passive"))
    )
    (net (code "6") (name "/Current_W2") (class "Default")
      (node (ref "Q12") (pin "3") (pinfunction "S_3") (pintype "passive"))
      (node (ref "R18") (pin "2") (pinfunction "2_2") (pintype "passive"))
      (node (ref "R47") (pin "1") (pintype "passive"))
    )
    (net (code "7") (name "/ENCA1") (class "Default")
      (node (ref "R71") (pin "2") (pinfunction "2_2") (pintype "passive"))
    )
    (net (code "8") (name "/ENCA2") (class "Default")
      (node (ref "R80") (pin "2") (pinfunction "2_2") (pintype "passive"))
    )
    (net (code "9") (name "/ENCB1") (class "Default")
      (node (ref "R70") (pin "2") (pinfunction "2_2") (pintype "passive"))
    )
    (net (code "10") (name "/ENCB2") (class "Default")
      (node (ref "R79") (pin "2") (pinfunction "2_2") (pintype "passive"))
    )
    (net (code "11") (name "/ENCZ1") (class "Default")
      (node (ref "R69") (pin "2") (pinfunction "2_2") (pintype "passive"))
    )
    (net (code "12") (name "/ENCZ2") (class "Default")
      (node (ref "R78") (pin "2") (pinfunction "2_2") (pintype "passive"))
    )
    (net (code "13") (name "/HALLU1") (class "Default")
      (node (ref "C27") (pin "1") (pinfunction "1_1") (pintype "passive"))
      (node (ref "D21") (pin "1") (pinfunction "A_1") (pintype "passive"))
      (node (ref "R68") (pin "2") (pinfunction "2_2") (pintype "passive"))
    )
    (net (code "14") (name "/HALLU2") (class "Default")
      (node (ref "C33") (pin "1") (pinfunction "1_1") (pintype "passive"))
      (node (ref "D24") (pin "1") (pinfunction "A_1") (pintype "passive"))
      (node (ref "R77") (pin "2") (pinfunction "2_2") (pintype "passive"))
    )
    (net (code "15") (name "/HALLV1") (class "Default")
      (node (ref "C26") (pin "1") (pinfunction "1_1") (pintype "passive"))
      (node (ref "D20") (pin "1") (pinfunction "A_1") (pintype "passive"))
      (node (ref "R67") (pin "2") (pinfunction "2_2") (pintype "passive"))
    )
    (net (code "16") (name "/HALLV2") (class "Default")
      (node (ref "C32") (pin "1") (pinfunction "1_1") (pintype "passive"))
      (node (ref "D23") (pin "1") (pinfunction "A_1") (pintype "passive"))
      (node (ref "R76") (pin "2") (pinfunction "2_2") (pintype "passive"))
    )
    (net (code "17") (name "/HALLW1") (class "Default")
      (node (ref "C25") (pin "1") (pinfunction "1_1") (pintype "passive"))
      (node (ref "D19") (pin "1") (pinfunction "A_1") (pintype "passive"))
      (node (ref "R66") (pin "2") (pinfunction "2_2") (pintype "passive"))
    )
    (net (code "18") (name "/HALLW2") (class "Default")
      (node (ref "C31") (pin "1") (pinfunction "1_1") (pintype "passive"))
      (node (ref "D22") (pin "1") (pinfunction "A_1") (pintype "passive"))
      (node (ref "R75") (pin "2") (pinfunction "2_2") (pintype "passive"))
    )
    (net (code "19") (name "/HO11") (class "Default")
      (node (ref "D2") (pin "2") (pinfunction "K_2") (pintype "passive"))
      (node (ref "R1") (pin "1") (pinfunction "1_1") (pintype "passive"))
      (node (ref "U1") (pin "19") (pinfunction "HO1_19") (pintype "passive"))
    )
    (net (code "20") (name "/HO12") (class "Default")
      (node (ref "D11") (pin "2") (pinfunction "K_2") (pintype "passive"))
      (node (ref "R10") (pin "1") (pinfunction "1_1") (pintype "passive"))
      (node (ref "U2") (pin "19") (pinfunction "HO1_19") (pintype "passive"))
    )
    (net (code "21") (name "/HO21") (class "Default")
      (node (ref "D5") (pin "2") (pinfunction "K_2") (pintype "passive"))
      (node (ref "R4") (pin "1") (pinfunction "1_1") (pintype "passive"))
      (node (ref "U1") (pin "16") (pinfunction "HO2_16") (pintype "passive"))
    )
    (net (code "22") (name "/HO22") (class "Default")
      (node (ref "D14") (pin "2") (pinfunction "K_2") (pintype "passive"))
      (node (ref "R13") (pin "1") (pinfunction "1_1") (pintype "passive"))
      (node (ref "U2") (pin "16") (pinfunction "HO2_16") (pintype "passive"))
    )
    (net (code "23") (name "/HO31") (class "Default")
      (node (ref "D8") (pin "2") (pinfunction "K_2") (pintype "passive"))
      (node (ref "R7") (pin "1") (pinfunction "1_1") (pintype "passive"))
      (node (ref "U1") (pin "13") (pinfunction "HO3_13") (pintype "passive"))
    )
    (net (code "24") (name "/HO32") (class "Default")
      (node (ref "D17") (pin "2") (pinfunction "K_2") (pintype "passive"))
      (node (ref "R16") (pin "1") (pinfunction "1_1") (pintype "passive"))
      (node (ref "U2") (pin "13") (pinfunction "HO3_13") (pintype "passive"))
    )
    (net (code "25") (name "/INA+1") (class "Default")
      (node (ref "C15") (pin "1") (pintype "passive"))
      (node (ref "R19") (pin "2") (pintype "passive"))
      (node (ref "R20") (pin "1") (pintype "passive"))
      (node (ref "U7") (pin "3") (pinfunction "INA+_3") (pintype "passive"))
    )
    (net (code "26") (name "/INA+2") (class "Default")
      (node (ref "C21") (pin "1") (pintype "passive"))
      (node (ref "R39") (pin "2") (pintype "passive"))
      (node (ref "R40") (pin "1") (pintype "passive"))
      (node (ref "U8") (pin "3") (pinfunction "INA+_3") (pintype "passive"))
    )
    (net (code "27") (name "/INA-1") (class "Default")
      (node (ref "R23") (pin "2") (pintype "passive"))
      (node (ref "R29") (pin "2") (pintype "passive"))
      (node (ref "R35") (pin "2") (pintype "passive"))
      (node (ref "U7") (pin "1") (pinfunction "OUTA_1") (pintype "passive"))
      (node (ref "U7") (pin "2") (pinfunction "INA-_2") (pintype "passive"))
    )
    (net (code "28") (name "/INA-2") (class "Default")
      (node (ref "R43") (pin "2") (pintype "passive"))
      (node (ref "R49") (pin "2") (pintype "passive"))
      (node (ref "R55") (pin "2") (pintype "passive"))
      (node (ref "U8") (pin "1") (pinfunction "OUTA_1") (pintype "passive"))
      (node (ref "U8") (pin "2") (pinfunction "INA-_2") (pintype "passive"))
    )
    (net (code "29") (name "/INB+1") (class "Default")
      (node (ref "R22") (pin "2") (pintype "passive"))
      (node (ref "R23") (pin "1") (pintype "passive"))
      (node (ref "U7") (pin "5") (pinfunction "INB+_5") (pintype "passive"))
    )
    (net (code "30") (name "/INB+2") (class "Default")
      (node (ref "R42") (pin "2") (pintype "passive"))
      (node (ref "R43") (pin "1") (pintype "passive"))
      (node (ref "U8") (pin "5") (pinfunction "INB+_5") (pintype "passive"))
    )
    (net (code "31") (name "/INB-1") (class "Default")
      (node (ref "R25") (pin "2") (pintype "passive"))
      (node (ref "R26") (pin "1") (pintype "passive"))
      (node (ref "U7") (pin "6") (pinfunction "INB-_6") (pintype "passive"))
    )
    (net (code "32") (name "/INB-2") (class "Default")
      (node (ref "R45") (pin "2") (pintype "passive"))
      (node (ref "R46") (pin "1") (pintype "passive"))
      (node (ref "U8") (pin "6") (pinfunction "INB-_6") (pintype "passive"))
    )
    (net (code "33") (name "/INC+1") (class "Default")
      (node (ref "R28") (pin "2") (pintype "passive"))
      (node (ref "R29") (pin "1") (pintype "passive"))
      (node (ref "U7") (pin "10") (pinfunction "INC+_10") (pintype "passive"))
    )
    (net (code "34") (name "/INC+2") (class "Default")
      (node (ref "R48") (pin "2") (pintype "passive"))
      (node (ref "R49") (pin "1") (pintype "passive"))
      (node (ref "U8") (pin "10") (pinfunction "INC+_10") (pintype "passive"))
    )
    (net (code "35") (name "/INC-1") (class "Default")
      (node (ref "R31") (pin "2") (pintype "passive"))
      (node (ref "R32") (pin "1") (pintype "passive"))
      (node (ref "U7") (pin "9") (pinfunction "INC-_9") (pintype "passive"))
    )
    (net (code "36") (name "/INC-2") (class "Default")
      (node (ref "R51") (pin "2") (pintype "passive"))
      (node (ref "R52") (pin "1") (pintype "passive"))
      (node (ref "U8") (pin "9") (pinfunction "INC-_9") (pintype "passive"))
    )
    (net (code "37") (name "/IND+1") (class "Default")
      (node (ref "R34") (pin "2") (pintype "passive"))
      (node (ref "R35") (pin "1") (pintype "passive"))
      (node (ref "U7") (pin "12") (pinfunction "IND+_12") (pintype "passive"))
    )
    (net (code "38") (name "/IND+2") (class "Default")
      (node (ref "R54") (pin "2") (pintype "passive"))
      (node (ref "R55") (pin "1") (pintype "passive"))
      (node (ref "U8") (pin "12") (pinfunction "IND+_12") (pintype "passive"))
    )
    (net (code "39") (name "/IND-1") (class "Default")
      (node (ref "R37") (pin "2") (pintype "passive"))
      (node (ref "R38") (pin "1") (pintype "passive"))
      (node (ref "U7") (pin "13") (pinfunction "IND-_13") (pintype "passive"))
    )
    (net (code "40") (name "/IND-2") (class "Default")
      (node (ref "R57") (pin "2") (pintype "passive"))
      (node (ref "R58") (pin "1") (pintype "passive"))
      (node (ref "U8") (pin "13") (pinfunction "IND-_13") (pintype "passive"))
    )
    (net (code "41") (name "/LO11") (class "Default")
      (node (ref "D3") (pin "2") (pinfunction "K_2") (pintype "passive"))
      (node (ref "R2") (pin "1") (pinfunction "1_1") (pintype "passive"))
      (node (ref "U1") (pin "11") (pinfunction "LO1_11") (pintype "passive"))
    )
    (net (code "42") (name "/LO12") (class "Default")
      (node (ref "D12") (pin "2") (pinfunction "K_2") (pintype "passive"))
      (node (ref "R11") (pin "1") (pinfunction "1_1") (pintype "passive"))
      (node (ref "U2") (pin "11") (pinfunction "LO1_11") (pintype "passive"))
    )
    (net (code "43") (name "/LO21") (class "Default")
      (node (ref "D6") (pin "2") (pinfunction "K_2") (pintype "passive"))
      (node (ref "R5") (pin "1") (pinfunction "1_1") (pintype "passive"))
      (node (ref "U1") (pin "10") (pinfunction "LO2_10") (pintype "passive"))
    )
    (net (code "44") (name "/LO22") (class "Default")
      (node (ref "D15") (pin "2") (pinfunction "K_2") (pintype "passive"))
      (node (ref "R14") (pin "1") (pinfunction "1_1") (pintype "passive"))
      (node (ref "U2") (pin "10") (pinfunction "LO2_10") (pintype "passive"))
    )
    (net (code "45") (name "/LO31") (class "Default")
      (node (ref "D9") (pin "2") (pinfunction "K_2") (pintype "passive"))
      (node (ref "R8") (pin "1") (pinfunction "1_1") (pintype "passive"))
      (node (ref "U1") (pin "9") (pinfunction "LO3_9") (pintype "passive"))
    )
    (net (code "46") (name "/LO32") (class "Default")
      (node (ref "D18") (pin "2") (pinfunction "K_2") (pintype "passive"))
      (node (ref "R17") (pin "1") (pinfunction "1_1") (pintype "passive"))
      (node (ref "U2") (pin "9") (pinfunction "LO3_9") (pintype "passive"))
    )
    (net (code "47") (name "/Motor_U1") (class "Default")
      (node (ref "C1") (pin "1") (pinfunction "1_1") (pintype "passive"))
      (node (ref "CN3") (pin "1") (pinfunction "1_1") (pintype "passive"))
      (node (ref "Q1") (pin "3") (pinfunction "S_3") (pintype "passive"))
      (node (ref "Q2") (pin "2") (pinfunction "D_2") (pintype "passive"))
      (node (ref "U1") (pin "18") (pinfunction "VS1_18") (pintype "passive"))
    )
    (net (code "48") (name "/Motor_U2") (class "Default")
      (node (ref "C7") (pin "1") (pinfunction "1_1") (pintype "passive"))
      (node (ref "CN3") (pin "4") (pinfunction "4_4") (pintype "passive"))
      (node (ref "Q7") (pin "3") (pinfunction "S_3") (pintype "passive"))
      (node (ref "Q8") (pin "2") (pinfunction "D_2") (pintype "passive"))
      (node (ref "U2") (pin "18") (pinfunction "VS1_18") (pintype "passive"))
    )
    (net (code "49") (name "/Motor_V1") (class "Default")
      (node (ref "C3") (pin "1") (pinfunction "1_1") (pintype "passive"))
      (node (ref "CN3") (pin "2") (pinfunction "2_2") (pintype "passive"))
      (node (ref "Q3") (pin "3") (pinfunction "S_3") (pintype "passive"))
      (node (ref "Q4") (pin "2") (pinfunction "D_2") (pintype "passive"))
      (node (ref "U1") (pin "15") (pinfunction "VS2_15") (pintype "passive"))
    )
    (net (code "50") (name "/Motor_V2") (class "Default")
      (node (ref "C9") (pin "1") (pinfunction "1_1") (pintype "passive"))
      (node (ref "CN3") (pin "5") (pinfunction "5_5") (pintype "passive"))
      (node (ref "Q10") (pin "2") (pinfunction "D_2") (pintype "passive"))
      (node (ref "Q9") (pin "3") (pinfunction "S_3") (pintype "passive"))
      (node (ref "U2") (pin "15") (pinfunction "VS2_15") (pintype "passive"))
    )
    (net (code "51") (name "/Motor_W1") (class "Default")
      (node (ref "C5") (pin "1") (pinfunction "1_1") (pintype "passive"))
      (node (ref "CN3") (pin "3") (pinfunction "3_3") (pintype "passive"))
      (node (ref "Q5") (pin "3") (pinfunction "S_3") (pintype "passive"))
      (node (ref "Q6") (pin "2") (pinfunction "D_2") (pintype "passive"))
      (node (ref "U1") (pin "12") (pinfunction "VS3_12") (pintype "passive"))
    )
    (net (code "52") (name "/Motor_W2") (class "Default")
      (node (ref "C11") (pin "1") (pinfunction "1_1") (pintype "passive"))
      (node (ref "CN3") (pin "6") (pinfunction "6_6") (pintype "passive"))
      (node (ref "Q11") (pin "3") (pinfunction "S_3") (pintype "passive"))
      (node (ref "Q12") (pin "2") (pinfunction "D_2") (pintype "passive"))
      (node (ref "U2") (pin "12") (pinfunction "VS3_12") (pintype "passive"))
    )
    (net (code "53") (name "/OUTB1") (class "Default")
      (node (ref "R26") (pin "2") (pintype "passive"))
      (node (ref "U7") (pin "7") (pinfunction "OUTB_7") (pintype "passive"))
    )
    (net (code "54") (name "/OUTB2") (class "Default")
      (node (ref "R46") (pin "2") (pintype "passive"))
      (node (ref "U8") (pin "7") (pinfunction "OUTB_7") (pintype "passive"))
    )
    (net (code "55") (name "/OUTC1") (class "Default")
      (node (ref "R32") (pin "2") (pintype "passive"))
      (node (ref "U7") (pin "8") (pinfunction "OUTC_8") (pintype "passive"))
    )
    (net (code "56") (name "/OUTC2") (class "Default")
      (node (ref "R52") (pin "2") (pintype "passive"))
      (node (ref "U8") (pin "8") (pinfunction "OUTC_8") (pintype "passive"))
    )
    (net (code "57") (name "/OUTD1") (class "Default")
      (node (ref "R38") (pin "2") (pintype "passive"))
      (node (ref "U7") (pin "14") (pinfunction "OUTD_14") (pintype "passive"))
    )
    (net (code "58") (name "/OUTD2") (class "Default")
      (node (ref "R58") (pin "2") (pintype "passive"))
      (node (ref "U8") (pin "14") (pinfunction "OUTD_14") (pintype "passive"))
    )
    (net (code "59") (name "/PA5") (class "Default")
      (node (ref "U2") (pin "4") (pinfunction "LIN1_4") (pintype "passive"))
    )
    (net (code "61") (name "/PA8") (class "Default")
      (node (ref "U1") (pin "1") (pinfunction "HIN1_1") (pintype "passive"))
    )
    (net (code "62") (name "/PA9") (class "Default")
      (node (ref "U1") (pin "2") (pinfunction "HIN2_2") (pintype "passive"))
    )
    (net (code "63") (name "/PA10") (class "Default")
      (node (ref "U1") (pin "3") (pinfunction "HIN3_3") (pintype "passive"))
    )
    (net (code "64") (name "/PB0") (class "Default")
      (node (ref "U2") (pin "5") (pinfunction "LIN2_5") (pintype "passive"))
    )
    (net (code "65") (name "/PB1") (class "Default")
      (node (ref "U2") (pin "6") (pinfunction "LIN3_6") (pintype "passive"))
    )
    (net (code "66") (name "/PB13") (class "Default")
      (node (ref "U1") (pin "4") (pinfunction "LIN1_4") (pintype "passive"))
    )
    (net (code "67") (name "/PB14") (class "Default")
      (node (ref "U1") (pin "5") (pinfunction "LIN2_5") (pintype "passive"))
    )
    (net (code "68") (name "/PB15") (class "Default")
      (node (ref "U1") (pin "6") (pinfunction "LIN3_6") (pintype "passive"))
    )
    (net (code "69") (name "/PC6") (class "Default")
      (node (ref "U2") (pin "1") (pinfunction "HIN1_1") (pintype "passive"))
    )
    (net (code "70") (name "/PC7") (class "Default")
      (node (ref "U2") (pin "2") (pinfunction "HIN2_2") (pintype "passive"))
    )
    (net (code "71") (name "/PC8") (class "Default")
      (node (ref "U2") (pin "3") (pinfunction "HIN3_3") (pintype "passive"))
    )
    (net (code "72") (name "/VB11") (class "Default")
      (node (ref "C1") (pin "2") (pinfunction "2_2") (pintype "passive"))
      (node (ref "D1") (pin "2") (pinfunction "K_2") (pintype "passive"))
      (node (ref "U1") (pin "20") (pinfunction "VB1_20") (pintype "passive"))
    )
    (net (code "73") (name "/VB12") (class "Default")
      (node (ref "C7") (pin "2") (pinfunction "2_2") (pintype "passive"))
      (node (ref "D10") (pin "2") (pinfunction "K_2") (pintype "passive"))
      (node (ref "U2") (pin "20") (pinfunction "VB1_20") (pintype "passive"))
    )
    (net (code "74") (name "/VB21") (class "Default")
      (node (ref "C3") (pin "2") (pinfunction "2_2") (pintype "passive"))
      (node (ref "D4") (pin "2") (pinfunction "K_2") (pintype "passive"))
      (node (ref "U1") (pin "17") (pinfunction "VB2_17") (pintype "passive"))
    )
    (net (code "75") (name "/VB22") (class "Default")
      (node (ref "C9") (pin "2") (pinfunction "2_2") (pintype "passive"))
      (node (ref "D13") (pin "2") (pinfunction "K_2") (pintype "passive"))
      (node (ref "U2") (pin "17") (pinfunction "VB2_17") (pintype "passive"))
    )
    (net (code "76") (name "/VB31") (class "Default")
      (node (ref "C5") (pin "2") (pinfunction "2_2") (pintype "passive"))
      (node (ref "D7") (pin "2") (pinfunction "K_2") (pintype "passive"))
      (node (ref "U1") (pin "14") (pinfunction "VB3_14") (pintype "passive"))
    )
    (net (code "77") (name "/VB32") (class "Default")
      (node (ref "C11") (pin "2") (pinfunction "2_2") (pintype "passive"))
      (node (ref "D16") (pin "2") (pinfunction "K_2") (pintype "passive"))
      (node (ref "U2") (pin "14") (pinfunction "VB3_14") (pintype "passive"))
    )
    (net (code "78") (name "DGND") (class "Default")
      (node (ref "C13") (pin "1") (pintype "passive"))
      (node (ref "C14") (pin "1") (pintype "passive"))
      (node (ref "C15") (pin "2") (pintype "passive"))
      (node (ref "C19") (pin "1") (pintype "passive"))
      (node (ref "C2") (pin "1") (pinfunction "1_1") (pintype "passive"))
      (node (ref "C20") (pin "1") (pintype "passive"))
      (node (ref "C21") (pin "2") (pintype "passive"))
      (node (ref "C25") (pin "2") (pinfunction "2_2") (pintype "passive"))
      (node (ref "C26") (pin "2") (pinfunction "2_2") (pintype "passive"))
      (node (ref "C27") (pin "2") (pinfunction "2_2") (pintype "passive"))
      (node (ref "C28") (pin "2") (pinfunction "2_2") (pintype "passive"))
      (node (ref "C29") (pin "2") (pinfunction "2_2") (pintype "passive"))
      (node (ref "C30") (pin "2") (pinfunction "2_2") (pintype "passive"))
      (node (ref "C31") (pin "2") (pinfunction "2_2") (pintype "passive"))
      (node (ref "C32") (pin "2") (pinfunction "2_2") (pintype "passive"))
      (node (ref "C33") (pin "2") (pinfunction "2_2") (pintype "passive"))
      (node (ref "C34") (pin "2") (pinfunction "2_2") (pintype "passive"))
      (node (ref "C35") (pin "2") (pinfunction "2_2") (pintype "passive"))
      (node (ref "C36") (pin "2") (pinfunction "2_2") (pintype "passive"))
      (node (ref "C4") (pin "1") (pinfunction "1_1") (pintype "passive"))
      (node (ref "C56") (pin "2") (pinfunction "K_2") (pintype "passive"))
      (node (ref "C57") (pin "2") (pinfunction "2_2") (pintype "passive"))
      (node (ref "C58") (pin "2") (pinfunction "2_2") (pintype "passive"))
      (node (ref "C60") (pin "2") (pinfunction "2_2") (pintype "passive"))
      (node (ref "C61") (pin "2") (pinfunction "K_2") (pintype "passive"))
      (node (ref "C62") (pin "2") (pinfunction "2_2") (pintype "passive"))
      (node (ref "C63") (pin "2") (pinfunction "2_2") (pintype "passive"))
      (node (ref "C64") (pin "2") (pinfunction "2_2") (pintype "passive"))
      (node (ref "C68") (pin "2") (pinfunction "2_2") (pintype "passive"))
      (node (ref "C69") (pin "2") (pinfunction "2_2") (pintype "passive"))
      (node (ref "C88") (pin "2") (pinfunction "K_2") (pintype "passive"))
      (node (ref "C90") (pin "2") (pinfunction "2_2") (pintype "passive"))
      (node (ref "C91") (pin "2") (pinfunction "2_2") (pintype "passive"))
      (node (ref "C92") (pin "2") (pinfunction "K_2") (pintype "passive"))
      (node (ref "C93") (pin "2") (pinfunction "2_2") (pintype "passive"))
      (node (ref "C95") (pin "2") (pinfunction "2_2") (pintype "passive"))
      (node (ref "CN1") (pin "4") (pinfunction "4_4") (pintype "passive"))
      (node (ref "CN2") (pin "4") (pinfunction "4_4") (pintype "passive"))
      (node (ref "CN3") (pin "8") (pinfunction "8_8") (pintype "passive"))
      (node (ref "D27") (pin "1") (pintype "passive"))
      (node (ref "Hole1") (pin "0") (pinfunction "PAD_0") (pintype "passive"))
      (node (ref "Hole2") (pin "0") (pinfunction "PAD_0") (pintype "passive"))
      (node (ref "Hole3") (pin "0") (pinfunction "PAD_0") (pintype "passive"))
      (node (ref "Hole4") (pin "0") (pinfunction "PAD_0") (pintype "passive"))
      (node (ref "R12") (pin "1") (pinfunction "1_1") (pintype "passive"))
      (node (ref "R15") (pin "1") (pinfunction "1_1") (pintype "passive"))
      (node (ref "R18") (pin "1") (pinfunction "1_1") (pintype "passive"))
      (node (ref "R20") (pin "2") (pintype "passive"))
      (node (ref "R24") (pin "1") (pintype "passive"))
      (node (ref "R3") (pin "1") (pinfunction "1_1") (pintype "passive"))
      (node (ref "R30") (pin "1") (pintype "passive"))
      (node (ref "R36") (pin "1") (pintype "passive"))
      (node (ref "R40") (pin "2") (pintype "passive"))
      (node (ref "R44") (pin "1") (pintype "passive"))
      (node (ref "R50") (pin "1") (pintype "passive"))
      (node (ref "R56") (pin "1") (pintype "passive"))
      (node (ref "R6") (pin "1") (pinfunction "1_1") (pintype "passive"))
      (node (ref "R62") (pin "2") (pinfunction "2_2") (pintype "passive"))
      (node (ref "R9") (pin "1") (pinfunction "1_1") (pintype "passive"))
      (node (ref "U1") (pin "8") (pinfunction "COM_8") (pintype "passive"))
      (node (ref "U12") (pin "2") (pinfunction "GND_2") (pintype "passive"))
      (node (ref "U13") (pin "1") (pinfunction "GND_1") (pintype "passive"))
      (node (ref "U14") (pin "2") (pinfunction "GND_2") (pintype "passive"))
      (node (ref "U2") (pin "8") (pinfunction "COM_8") (pintype "passive"))
      (node (ref "U7") (pin "11") (pinfunction "VSS_11") (pintype "passive"))
      (node (ref "U8") (pin "11") (pinfunction "VSS_11") (pintype "passive"))
    )
    (net (code "79") (name "Net-(C16-Pad1)") (class "Default")
      (node (ref "C16") (pin "1") (pintype "passive"))
      (node (ref "R21") (pin "2") (pintype "passive"))
      (node (ref "R22") (pin "1") (pintype "passive"))
    )
    (net (code "80") (name "Net-(C16-Pad2)") (class "Default")
      (node (ref "C16") (pin "2") (pintype "passive"))
      (node (ref "R24") (pin "2") (pintype "passive"))
      (node (ref "R25") (pin "1") (pintype "passive"))
    )
    (net (code "81") (name "Net-(C17-Pad1)") (class "Default")
      (node (ref "C17") (pin "1") (pintype "passive"))
      (node (ref "R27") (pin "2") (pintype "passive"))
      (node (ref "R28") (pin "1") (pintype "passive"))
    )
    (net (code "82") (name "Net-(C17-Pad2)") (class "Default")
      (node (ref "C17") (pin "2") (pintype "passive"))
      (node (ref "R30") (pin "2") (pintype "passive"))
      (node (ref "R31") (pin "1") (pintype "passive"))
    )
    (net (code "83") (name "Net-(C18-Pad1)") (class "Default")
      (node (ref "C18") (pin "1") (pintype "passive"))
      (node (ref "R33") (pin "2") (pintype "passive"))
      (node (ref "R34") (pin "1") (pintype "passive"))
    )
    (net (code "84") (name "Net-(C18-Pad2)") (class "Default")
      (node (ref "C18") (pin "2") (pintype "passive"))
      (node (ref "R36") (pin "2") (pintype "passive"))
      (node (ref "R37") (pin "1") (pintype "passive"))
    )
    (net (code "85") (name "Net-(C22-Pad1)") (class "Default")
      (node (ref "C22") (pin "1") (pintype "passive"))
      (node (ref "R41") (pin "2") (pintype "passive"))
      (node (ref "R42") (pin "1") (pintype "passive"))
    )
    (net (code "86") (name "Net-(C22-Pad2)") (class "Default")
      (node (ref "C22") (pin "2") (pintype "passive"))
      (node (ref "R44") (pin "2") (pintype "passive"))
      (node (ref "R45") (pin "1") (pintype "passive"))
    )
    (net (code "87") (name "Net-(C23-Pad1)") (class "Default")
      (node (ref "C23") (pin "1") (pintype "passive"))
      (node (ref "R47") (pin "2") (pintype "passive"))
      (node (ref "R48") (pin "1") (pintype "passive"))
    )
    (net (code "88") (name "Net-(C23-Pad2)") (class "Default")
      (node (ref "C23") (pin "2") (pintype "passive"))
      (node (ref "R50") (pin "2") (pintype "passive"))
      (node (ref "R51") (pin "1") (pintype "passive"))
    )
    (net (code "89") (name "Net-(C24-Pad1)") (class "Default")
      (node (ref "C24") (pin "1") (pintype "passive"))
      (node (ref "R53") (pin "2") (pintype "passive"))
      (node (ref "R54") (pin "1") (pintype "passive"))
    )
    (net (code "90") (name "Net-(C24-Pad2)") (class "Default")
      (node (ref "C24") (pin "2") (pintype "passive"))
      (node (ref "R56") (pin "2") (pintype "passive"))
      (node (ref "R57") (pin "1") (pintype "passive"))
    )
    (net (code "91") (name "Net-(C28-Pad1)") (class "Default")
      (node (ref "C28") (pin "1") (pinfunction "1_1") (pintype "passive"))
      (node (ref "CN1") (pin "8") (pinfunction "8_8") (pintype "passive"))
      (node (ref "R71") (pin "1") (pinfunction "1_1") (pintype "passive"))
    )
    (net (code "92") (name "Net-(C29-Pad1)") (class "Default")
      (node (ref "C29") (pin "1") (pinfunction "1_1") (pintype "passive"))
      (node (ref "CN1") (pin "7") (pinfunction "7_7") (pintype "passive"))
      (node (ref "R70") (pin "1") (pinfunction "1_1") (pintype "passive"))
    )
    (net (code "93") (name "Net-(C30-Pad1)") (class "Default")
      (node (ref "C30") (pin "1") (pinfunction "1_1") (pintype "passive"))
      (node (ref "CN1") (pin "6") (pinfunction "6_6") (pintype "passive"))
      (node (ref "R69") (pin "1") (pinfunction "1_1") (pintype "passive"))
    )
    (net (code "94") (name "Net-(C34-Pad1)") (class "Default")
      (node (ref "C34") (pin "1") (pinfunction "1_1") (pintype "passive"))
      (node (ref "CN2") (pin "8") (pinfunction "8_8") (pintype "passive"))
      (node (ref "R80") (pin "1") (pinfunction "1_1") (pintype "passive"))
    )
    (net (code "95") (name "Net-(C35-Pad1)") (class "Default")
      (node (ref "C35") (pin "1") (pinfunction "1_1") (pintype "passive"))
      (node (ref "CN2") (pin "7") (pinfunction "7_7") (pintype "passive"))
      (node (ref "R79") (pin "1") (pinfunction "1_1") (pintype "passive"))
    )
    (net (code "96") (name "Net-(C36-Pad1)") (class "Default")
      (node (ref "C36") (pin "1") (pinfunction "1_1") (pintype "passive"))
      (node (ref "CN2") (pin "6") (pinfunction "6_6") (pintype "passive"))
      (node (ref "R78") (pin "1") (pinfunction "1_1") (pintype "passive"))
    )
    (net (code "97") (name "Net-(C59-Pad1)") (class "Default")
      (node (ref "C59") (pin "1") (pinfunction "1_1") (pintype "passive"))
      (node (ref "R60") (pin "2") (pinfunction "2_2") (pintype "passive"))
    )
    (net (code "98") (name "Net-(CN1-Pad1)") (class "Default")
      (node (ref "CN1") (pin "1") (pinfunction "1_1") (pintype "passive"))
      (node (ref "R63") (pin "2") (pinfunction "2_2") (pintype "passive"))
      (node (ref "R66") (pin "1") (pinfunction "1_1") (pintype "passive"))
    )
    (net (code "99") (name "Net-(CN1-Pad2)") (class "Default")
      (node (ref "CN1") (pin "2") (pinfunction "2_2") (pintype "passive"))
      (node (ref "R64") (pin "2") (pinfunction "2_2") (pintype "passive"))
      (node (ref "R67") (pin "1") (pinfunction "1_1") (pintype "passive"))
    )
    (net (code "100") (name "Net-(CN1-Pad3)") (class "Default")
      (node (ref "CN1") (pin "3") (pinfunction "3_3") (pintype "passive"))
      (node (ref "R65") (pin "2") (pinfunction "2_2") (pintype "passive"))
      (node (ref "R68") (pin "1") (pinfunction "1_1") (pintype "passive"))
    )
    (net (code "101") (name "Net-(CN2-Pad1)") (class "Default")
      (node (ref "CN2") (pin "1") (pinfunction "1_1") (pintype "passive"))
      (node (ref "R72") (pin "2") (pinfunction "2_2") (pintype "passive"))
      (node (ref "R75") (pin "1") (pinfunction "1_1") (pintype "passive"))
    )
    (net (code "102") (name "Net-(CN2-Pad2)") (class "Default")
      (node (ref "CN2") (pin "2") (pinfunction "2_2") (pintype "passive"))
      (node (ref "R73") (pin "2") (pinfunction "2_2") (pintype "passive"))
      (node (ref "R76") (pin "1") (pinfunction "1_1") (pintype "passive"))
    )
    (net (code "103") (name "Net-(CN2-Pad3)") (class "Default")
      (node (ref "CN2") (pin "3") (pinfunction "3_3") (pintype "passive"))
      (node (ref "R74") (pin "2") (pinfunction "2_2") (pintype "passive"))
      (node (ref "R77") (pin "1") (pinfunction "1_1") (pintype "passive"))
    )
    (net (code "104") (name "Net-(D2-A)") (class "Default")
      (node (ref "D2") (pin "1") (pinfunction "A_1") (pintype "passive"))
      (node (ref "Q1") (pin "1") (pinfunction "G_1") (pintype "passive"))
      (node (ref "R1") (pin "2") (pinfunction "2_2") (pintype "passive"))
    )
    (net (code "105") (name "Net-(D3-A)") (class "Default")
      (node (ref "D3") (pin "1") (pinfunction "A_1") (pintype "passive"))
      (node (ref "Q2") (pin "1") (pinfunction "G_1") (pintype "passive"))
      (node (ref "R2") (pin "2") (pinfunction "2_2") (pintype "passive"))
    )
    (net (code "106") (name "Net-(D5-A)") (class "Default")
      (node (ref "D5") (pin "1") (pinfunction "A_1") (pintype "passive"))
      (node (ref "Q3") (pin "1") (pinfunction "G_1") (pintype "passive"))
      (node (ref "R4") (pin "2") (pinfunction "2_2") (pintype "passive"))
    )
    (net (code "107") (name "Net-(D6-A)") (class "Default")
      (node (ref "D6") (pin "1") (pinfunction "A_1") (pintype "passive"))
      (node (ref "Q4") (pin "1") (pinfunction "G_1") (pintype "passive"))
      (node (ref "R5") (pin "2") (pinfunction "2_2") (pintype "passive"))
    )
    (net (code "108") (name "Net-(D8-A)") (class "Default")
      (node (ref "D8") (pin "1") (pinfunction "A_1") (pintype "passive"))
      (node (ref "Q5") (pin "1") (pinfunction "G_1") (pintype "passive"))
      (node (ref "R7") (pin "2") (pinfunction "2_2") (pintype "passive"))
    )
    (net (code "109") (name "Net-(D9-A)") (class "Default")
      (node (ref "D9") (pin "1") (pinfunction "A_1") (pintype "passive"))
      (node (ref "Q6") (pin "1") (pinfunction "G_1") (pintype "passive"))
      (node (ref "R8") (pin "2") (pinfunction "2_2") (pintype "passive"))
    )
    (net (code "110") (name "Net-(D11-A)") (class "Default")
      (node (ref "D11") (pin "1") (pinfunction "A_1") (pintype "passive"))
      (node (ref "Q7") (pin "1") (pinfunction "G_1") (pintype "passive"))
      (node (ref "R10") (pin "2") (pinfunction "2_2") (pintype "passive"))
    )
    (net (code "111") (name "Net-(D12-A)") (class "Default")
      (node (ref "D12") (pin "1") (pinfunction "A_1") (pintype "passive"))
      (node (ref "Q8") (pin "1") (pinfunction "G_1") (pintype "passive"))
      (node (ref "R11") (pin "2") (pinfunction "2_2") (pintype "passive"))
    )
    (net (code "112") (name "Net-(D14-A)") (class "Default")
      (node (ref "D14") (pin "1") (pinfunction "A_1") (pintype "passive"))
      (node (ref "Q9") (pin "1") (pinfunction "G_1") (pintype "passive"))
      (node (ref "R13") (pin "2") (pinfunction "2_2") (pintype "passive"))
    )
    (net (code "113") (name "Net-(D15-A)") (class "Default")
      (node (ref "D15") (pin "1") (pinfunction "A_1") (pintype "passive"))
      (node (ref "Q10") (pin "1") (pinfunction "G_1") (pintype "passive"))
      (node (ref "R14") (pin "2") (pinfunction "2_2") (pintype "passive"))
    )
    (net (code "114") (name "Net-(D17-A)") (class "Default")
      (node (ref "D17") (pin "1") (pinfunction "A_1") (pintype "passive"))
      (node (ref "Q11") (pin "1") (pinfunction "G_1") (pintype "passive"))
      (node (ref "R16") (pin "2") (pinfunction "2_2") (pintype "passive"))
    )
    (net (code "115") (name "Net-(D18-A)") (class "Default")
      (node (ref "D18") (pin "1") (pinfunction "A_1") (pintype "passive"))
      (node (ref "Q12") (pin "1") (pinfunction "G_1") (pintype "passive"))
      (node (ref "R17") (pin "2") (pinfunction "2_2") (pintype "passive"))
    )
    (net (code "116") (name "Net-(D25-A)") (class "Default")
      (node (ref "CN3") (pin "7") (pinfunction "7_7") (pintype "passive"))
      (node (ref "D25") (pin "1") (pinfunction "A_1") (pintype "passive"))
      (node (ref "D26") (pin "1") (pinfunction "A_1") (pintype "passive"))
    )
    (net (code "117") (name "Net-(U13-BST)") (class "Default")
      (node (ref "C73") (pin "1") (pinfunction "1_1") (pintype "passive"))
      (node (ref "U13") (pin "6") (pinfunction "BST_6") (pintype "passive"))
    )
    (net (code "118") (name "Net-(U13-EN)") (class "Default")
      (node (ref "R59") (pin "2") (pinfunction "2_2") (pintype "passive"))
      (node (ref "U13") (pin "5") (pinfunction "EN_5") (pintype "passive"))
    )
    (net (code "119") (name "Net-(U13-FB)") (class "Default")
      (node (ref "R60") (pin "1") (pinfunction "1_1") (pintype "passive"))
      (node (ref "R61") (pin "1") (pinfunction "1_1") (pintype "passive"))
      (node (ref "R62") (pin "1") (pinfunction "1_1") (pintype "passive"))
      (node (ref "U13") (pin "4") (pinfunction "FB_4") (pintype "passive"))
    )
    (net (code "120") (name "Net-(U13-SW)") (class "Default")
      (node (ref "C73") (pin "2") (pinfunction "2_2") (pintype "passive"))
      (node (ref "L1") (pin "1") (pinfunction "1_1") (pintype "passive"))
      (node (ref "U13") (pin "2") (pinfunction "SW_2") (pintype "passive"))
    )
    (net (code "121") (name "POWER") (class "Default")
      (node (ref "D25") (pin "2") (pinfunction "K_2") (pintype "passive"))
      (node (ref "D26") (pin "2") (pinfunction "K_2") (pintype "passive"))
      (node (ref "D27") (pin "2") (pintype "passive"))
      (node (ref "Q1") (pin "2") (pinfunction "D_2") (pintype "passive"))
      (node (ref "Q11") (pin "2") (pinfunction "D_2") (pintype "passive"))
      (node (ref "Q3") (pin "2") (pinfunction "D_2") (pintype "passive"))
      (node (ref "Q5") (pin "2") (pinfunction "D_2") (pintype "passive"))
      (node (ref "Q7") (pin "2") (pinfunction "D_2") (pintype "passive"))
      (node (ref "Q9") (pin "2") (pinfunction "D_2") (pintype "passive"))
    )
    (net (code "122") (name "VCC3.3") (class "Default")
      (node (ref "C61") (pin "1") (pinfunction "A_1") (pintype "passive"))
      (node (ref "C62") (pin "1") (pinfunction "1_1") (pintype "passive"))
      (node (ref "C69") (pin "1") (pinfunction "1_1") (pintype "passive"))
      (node (ref "D19") (pin "2") (pinfunction "K_2") (pintype "passive"))
      (node (ref "D20") (pin "2") (pinfunction "K_2") (pintype "passive"))
      (node (ref "D21") (pin "2") (pinfunction "K_2") (pintype "passive"))
      (node (ref "D22") (pin "2") (pinfunction "K_2") (pintype "passive"))
      (node (ref "D23") (pin "2") (pinfunction "K_2") (pintype "passive"))
      (node (ref "D24") (pin "2") (pinfunction "K_2") (pintype "passive"))
      (node (ref "R63") (pin "1") (pinfunction "1_1") (pintype "passive"))
      (node (ref "R64") (pin "1") (pinfunction "1_1") (pintype "passive"))
      (node (ref "R65") (pin "1") (pinfunction "1_1") (pintype "passive"))
      (node (ref "R72") (pin "1") (pinfunction "1_1") (pintype "passive"))
      (node (ref "R73") (pin "1") (pinfunction "1_1") (pintype "passive"))
      (node (ref "R74") (pin "1") (pinfunction "1_1") (pintype "passive"))
      (node (ref "U12") (pin "5") (pinfunction "OUT_5") (pintype "passive"))
    )
    (net (code "123") (name "VCC5") (class "Default")
      (node (ref "C56") (pin "1") (pinfunction "A_1") (pintype "passive"))
      (node (ref "C57") (pin "1") (pinfunction "1_1") (pintype "passive"))
      (node (ref "C58") (pin "1") (pinfunction "1_1") (pintype "passive"))
      (node (ref "C59") (pin "2") (pinfunction "2_2") (pintype "passive"))
      (node (ref "C60") (pin "1") (pinfunction "1_1") (pintype "passive"))
      (node (ref "C68") (pin "1") (pinfunction "1_1") (pintype "passive"))
      (node (ref "C88") (pin "1") (pinfunction "A_1") (pintype "passive"))
      (node (ref "C90") (pin "1") (pinfunction "1_1") (pintype "passive"))
      (node (ref "C91") (pin "1") (pinfunction "1_1") (pintype "passive"))
      (node (ref "CN1") (pin "5") (pinfunction "5_5") (pintype "passive"))
      (node (ref "CN2") (pin "5") (pinfunction "5_5") (pintype "passive"))
      (node (ref "L1") (pin "2") (pinfunction "2_2") (pintype "passive"))
      (node (ref "R61") (pin "2") (pinfunction "2_2") (pintype "passive"))
      (node (ref "R84") (pin "2") (pinfunction "2_2") (pintype "passive"))
      (node (ref "U12") (pin "1") (pinfunction "VIN_1") (pintype "passive"))
      (node (ref "U12") (pin "3") (pinfunction "EN_3") (pintype "passive"))
      (node (ref "U14") (pin "1") (pinfunction "VIN_1") (pintype "passive"))
      (node (ref "U14") (pin "3") (pinfunction "EN_3") (pintype "passive"))
    )
    (net (code "124") (name "VCC11") (class "Default")
      (node (ref "C63") (pin "1") (pinfunction "1_1") (pintype "passive"))
      (node (ref "C64") (pin "1") (pinfunction "1_1") (pintype "passive"))
      (node (ref "D1") (pin "1") (pinfunction "A_1") (pintype "passive"))
      (node (ref "D10") (pin "1") (pinfunction "A_1") (pintype "passive"))
      (node (ref "D13") (pin "1") (pinfunction "A_1") (pintype "passive"))
      (node (ref "D16") (pin "1") (pinfunction "A_1") (pintype "passive"))
      (node (ref "D4") (pin "1") (pinfunction "A_1") (pintype "passive"))
      (node (ref "D7") (pin "1") (pinfunction "A_1") (pintype "passive"))
      (node (ref "R59") (pin "1") (pinfunction "1_1") (pintype "passive"))
      (node (ref "R85") (pin "1") (pinfunction "1_1") (pintype "passive"))
      (node (ref "U13") (pin "3") (pinfunction "VIN_3") (pintype "passive"))
    )
    (net (code "125") (name "VCCA3.3") (class "Default")
      (node (ref "C13") (pin "2") (pintype "passive"))
      (node (ref "C14") (pin "2") (pintype "passive"))
      (node (ref "C19") (pin "2") (pintype "passive"))
      (node (ref "C20") (pin "2") (pintype "passive"))
      (node (ref "C92") (pin "1") (pinfunction "A_1") (pintype "passive"))
      (node (ref "C93") (pin "1") (pinfunction "1_1") (pintype "passive"))
      (node (ref "C95") (pin "1") (pinfunction "1_1") (pintype "passive"))
      (node (ref "R19") (pin "1") (pintype "passive"))
      (node (ref "R39") (pin "1") (pintype "passive"))
      (node (ref "U14") (pin "5") (pinfunction "OUT_5") (pintype "passive"))
      (node (ref "U7") (pin "4") (pinfunction "VDD_4") (pintype "passive"))
      (node (ref "U8") (pin "4") (pinfunction "VDD_4") (pintype "passive"))
    )
    (net (code "126") (name "VCCDRV") (class "Default")
      (node (ref "C2") (pin "2") (pinfunction "2_2") (pintype "passive"))
      (node (ref "C4") (pin "2") (pinfunction "2_2") (pintype "passive"))
      (node (ref "R84") (pin "1") (pinfunction "1_1") (pintype "passive"))
      (node (ref "R85") (pin "2") (pinfunction "2_2") (pintype "passive"))
      (node (ref "U1") (pin "7") (pinfunction "VCC_7") (pintype "passive"))
      (node (ref "U2") (pin "7") (pinfunction "VCC_7") (pintype "passive"))
    )
    (net (code "127") (name "unconnected-(U12-BP-Pad4)") (class "Default")
      (node (ref "U12") (pin "4") (pinfunction "BP_4") (pintype "passive+no_connect"))
    )
    (net (code "128") (name "unconnected-(U14-BP-Pad4)") (class "Default")
      (node (ref "U14") (pin "4") (pinfunction "BP_4") (pintype "passive+no_connect"))
    )
  )
)
